# design.net
KiCad netlist of a schematic drawn in Altium Designer
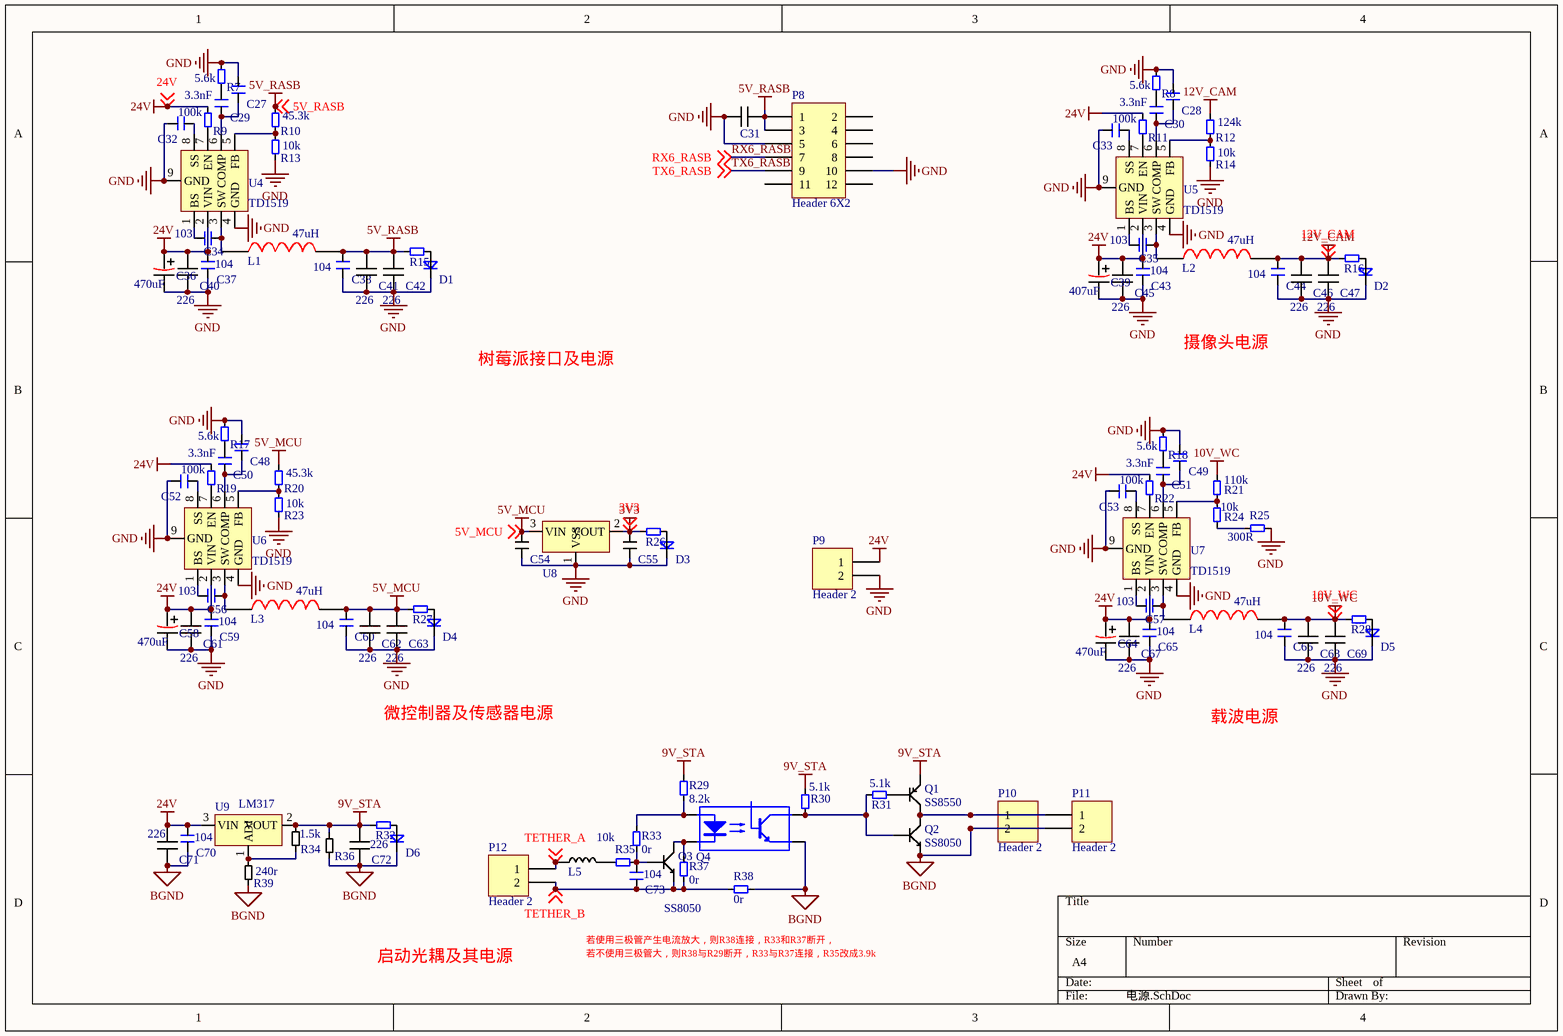
[diagram p0: 电源.SchDoc]

(export (version "E")
  (design (tool "Eeschema 10.0.6"))
  (components
    (comp (ref "C27") (value "0603C") (footprint "0603C") (libsource (lib "水下去机器人控制板2020") (part "0603C")))
    (comp (ref "C28") (value "0603C") (footprint "0603C") (libsource (lib "水下去机器人控制板2020") (part "0603C")))
    (comp (ref "C29")
      (value "0603C")
      (footprint "0603C")
      (fields (field (name "PARAMETER 1") "3.3nF"))
      (libsource (lib "水下去机器人控制板2020") (part "0603C"))
    )
    (comp (ref "C30")
      (value "0603C")
      (footprint "0603C")
      (fields (field (name "PARAMETER 1") "3.3nF"))
      (libsource (lib "水下去机器人控制板2020") (part "0603C"))
    )
    (comp (ref "C31") (value "1206C") (footprint "固态电容5*9") (libsource (lib "水下去机器人控制板2020") (part "1206C")))
    (comp (ref "C32") (value "0603C") (footprint "0603C") (libsource (lib "水下去机器人控制板2020") (part "0603C")))
    (comp (ref "C33") (value "0603C") (footprint "0603C") (libsource (lib "水下去机器人控制板2020") (part "0603C")))
    (comp (ref "C34")
      (value "0603C")
      (footprint "0603C")
      (fields (field (name "PARAMETER 1") "103"))
      (libsource (lib "水下去机器人控制板2020") (part "0603C"))
    )
    (comp (ref "C35")
      (value "0603C")
      (footprint "0603C")
      (fields (field (name "PARAMETER 1") "103"))
      (libsource (lib "水下去机器人控制板2020") (part "0603C"))
    )
    (comp (ref "C36")
      (value "10*10贴片电解电容")
      (footprint "CAP-10*10.2")
      (fields (field (name "PARAMETER 1") "470uF"))
      (libsource (lib "水下去机器人控制板2020") (part "10*10贴片电解电容"))
    )
    (comp (ref "C37")
      (value "0603C")
      (footprint "0603C")
      (fields (field (name "PARAMETER 1") "104"))
      (libsource (lib "水下去机器人控制板2020") (part "0603C"))
    )
    (comp (ref "C38")
      (value "0603C")
      (footprint "0603C")
      (fields (field (name "PARAMETER 1") "104"))
      (libsource (lib "水下去机器人控制板2020") (part "0603C"))
    )
    (comp (ref "C39")
      (value "10*10贴片电解电容")
      (footprint "CAP-10*10.2")
      (fields (field (name "PARAMETER 1") "407uF"))
      (libsource (lib "水下去机器人控制板2020") (part "10*10贴片电解电容"))
    )
    (comp (ref "C40")
      (value "1206C")
      (footprint "1206C")
      (fields (field (name "PARAMETER 1") "226"))
      (libsource (lib "水下去机器人控制板2020") (part "1206C"))
    )
    (comp (ref "C41")
      (value "1206C")
      (footprint "1206C")
      (fields (field (name "PARAMETER 1") "226"))
      (libsource (lib "水下去机器人控制板2020") (part "1206C"))
    )
    (comp (ref "C42")
      (value "1206C")
      (footprint "1206C")
      (fields (field (name "PARAMETER 1") "226"))
      (libsource (lib "水下去机器人控制板2020") (part "1206C"))
    )
    (comp (ref "C43")
      (value "0603C")
      (footprint "0603C")
      (fields (field (name "PARAMETER 1") "104"))
      (libsource (lib "水下去机器人控制板2020") (part "0603C"))
    )
    (comp (ref "C44")
      (value "0603C")
      (footprint "0603C")
      (fields (field (name "PARAMETER 1") "104"))
      (libsource (lib "水下去机器人控制板2020") (part "0603C"))
    )
    (comp (ref "C45")
      (value "1206C")
      (footprint "1206C")
      (fields (field (name "PARAMETER 1") "226"))
      (libsource (lib "水下去机器人控制板2020") (part "1206C"))
    )
    (comp (ref "C46")
      (value "1206C")
      (footprint "1206C")
      (fields (field (name "PARAMETER 1") "226"))
      (libsource (lib "水下去机器人控制板2020") (part "1206C"))
    )
    (comp (ref "C47")
      (value "1206C")
      (footprint "1206C")
      (fields (field (name "PARAMETER 1") "226"))
      (libsource (lib "水下去机器人控制板2020") (part "1206C"))
    )
    (comp (ref "C48") (value "0603C") (footprint "0603C") (libsource (lib "水下去机器人控制板2020") (part "0603C")))
    (comp (ref "C49") (value "0603C") (footprint "0603C") (libsource (lib "水下去机器人控制板2020") (part "0603C")))
    (comp (ref "C50")
      (value "0603C")
      (footprint "0603C")
      (fields (field (name "PARAMETER 1") "3.3nF"))
      (libsource (lib "水下去机器人控制板2020") (part "0603C"))
    )
    (comp (ref "C51")
      (value "0603C")
      (footprint "0603C")
      (fields (field (name "PARAMETER 1") "3.3nF"))
      (libsource (lib "水下去机器人控制板2020") (part "0603C"))
    )
    (comp (ref "C52") (value "0603C") (footprint "0603C") (libsource (lib "水下去机器人控制板2020") (part "0603C")))
    (comp (ref "C53") (value "0603C") (footprint "0603C") (libsource (lib "水下去机器人控制板2020") (part "0603C")))
    (comp (ref "C54") (value "0805C") (footprint "0805C") (libsource (lib "水下去机器人控制板2020") (part "0805C")))
    (comp (ref "C55") (value "0805C") (footprint "0805C") (libsource (lib "水下去机器人控制板2020") (part "0805C")))
    (comp (ref "C56")
      (value "0603C")
      (footprint "0603C")
      (fields (field (name "PARAMETER 1") "103"))
      (libsource (lib "水下去机器人控制板2020") (part "0603C"))
    )
    (comp (ref "C57")
      (value "0603C")
      (footprint "0603C")
      (fields (field (name "PARAMETER 1") "103"))
      (libsource (lib "水下去机器人控制板2020") (part "0603C"))
    )
    (comp (ref "C58")
      (value "10*10贴片电解电容")
      (footprint "CAP-10*10.2")
      (fields (field (name "PARAMETER 1") "470uF"))
      (libsource (lib "水下去机器人控制板2020") (part "10*10贴片电解电容"))
    )
    (comp (ref "C59")
      (value "0603C")
      (footprint "0603C")
      (fields (field (name "PARAMETER 1") "104"))
      (libsource (lib "水下去机器人控制板2020") (part "0603C"))
    )
    (comp (ref "C60")
      (value "0603C")
      (footprint "0603C")
      (fields (field (name "PARAMETER 1") "104"))
      (libsource (lib "水下去机器人控制板2020") (part "0603C"))
    )
    (comp (ref "C61")
      (value "1206C")
      (footprint "1206C")
      (fields (field (name "PARAMETER 1") "226"))
      (libsource (lib "水下去机器人控制板2020") (part "1206C"))
    )
    (comp (ref "C62")
      (value "1206C")
      (footprint "1206C")
      (fields (field (name "PARAMETER 1") "226"))
      (libsource (lib "水下去机器人控制板2020") (part "1206C"))
    )
    (comp (ref "C63")
      (value "1206C")
      (footprint "1206C")
      (fields (field (name "PARAMETER 1") "226"))
      (libsource (lib "水下去机器人控制板2020") (part "1206C"))
    )
    (comp (ref "C64")
      (value "10*10贴片电解电容")
      (footprint "CAP-10*10.2")
      (fields (field (name "PARAMETER 1") "470uF"))
      (libsource (lib "水下去机器人控制板2020") (part "10*10贴片电解电容"))
    )
    (comp (ref "C65")
      (value "0603C")
      (footprint "0603C")
      (fields (field (name "PARAMETER 1") "104"))
      (libsource (lib "水下去机器人控制板2020") (part "0603C"))
    )
    (comp (ref "C66")
      (value "0603C")
      (footprint "0603C")
      (fields (field (name "PARAMETER 1") "104"))
      (libsource (lib "水下去机器人控制板2020") (part "0603C"))
    )
    (comp (ref "C67")
      (value "1206C")
      (footprint "1206C")
      (fields (field (name "PARAMETER 1") "226"))
      (libsource (lib "水下去机器人控制板2020") (part "1206C"))
    )
    (comp (ref "C68")
      (value "1206C")
      (footprint "1206C")
      (fields (field (name "PARAMETER 1") "226"))
      (libsource (lib "水下去机器人控制板2020") (part "1206C"))
    )
    (comp (ref "C69")
      (value "1206C")
      (footprint "1206C")
      (fields (field (name "PARAMETER 1") "226"))
      (libsource (lib "水下去机器人控制板2020") (part "1206C"))
    )
    (comp (ref "C70")
      (value "0603C")
      (footprint "0603C")
      (fields (field (name "PARAMETER 1") "104"))
      (libsource (lib "水下去机器人控制板2020") (part "0603C"))
    )
    (comp (ref "C71")
      (value "1206C")
      (footprint "1206C")
      (fields (field (name "PARAMETER 1") "226"))
      (libsource (lib "水下去机器人控制板2020") (part "1206C"))
    )
    (comp (ref "C72")
      (value "1206C")
      (footprint "1206C")
      (fields (field (name "PARAMETER 1") "226"))
      (libsource (lib "水下去机器人控制板2020") (part "1206C"))
    )
    (comp (ref "C73")
      (value "0603C")
      (footprint "0603C")
      (fields (field (name "PARAMETER 1") "104"))
      (libsource (lib "水下去机器人控制板2020") (part "0603C"))
    )
    (comp (ref "D1") (value "0603D") (footprint "0603D") (libsource (lib "水下去机器人控制板2020") (part "0603D")))
    (comp (ref "D2") (value "0603D") (footprint "0603D") (libsource (lib "水下去机器人控制板2020") (part "0603D")))
    (comp (ref "D3") (value "0603D") (footprint "0603D") (libsource (lib "水下去机器人控制板2020") (part "0603D")))
    (comp (ref "D4") (value "0603D") (footprint "0603D") (libsource (lib "水下去机器人控制板2020") (part "0603D")))
    (comp (ref "D5") (value "0603D") (footprint "0603D") (libsource (lib "水下去机器人控制板2020") (part "0603D")))
    (comp (ref "D6") (value "0603D") (footprint "0603D") (libsource (lib "水下去机器人控制板2020") (part "0603D")))
    (comp (ref "L1")
      (value "1265L")
      (footprint "1265L")
      (fields (field (name "PARAMETER 1") "47uH"))
      (libsource (lib "水下去机器人控制板2020") (part "1265L"))
    )
    (comp (ref "L2")
      (value "1265L")
      (footprint "1265L")
      (fields (field (name "PARAMETER 1") "47uH"))
      (libsource (lib "水下去机器人控制板2020") (part "1265L"))
    )
    (comp (ref "L3")
      (value "1265L")
      (footprint "1265L")
      (fields (field (name "PARAMETER 1") "47uH"))
      (libsource (lib "水下去机器人控制板2020") (part "1265L"))
    )
    (comp (ref "L4")
      (value "1265L")
      (footprint "1265L")
      (fields (field (name "PARAMETER 1") "47uH"))
      (libsource (lib "水下去机器人控制板2020") (part "1265L"))
    )
    (comp (ref "L5") (value "0805L") (footprint "0805L") (libsource (lib "水下去机器人控制板2020") (part "0805L")))
    (comp (ref "P8")
      (value "Header 6X2")
      (footprint "HDR2X6")
      (description "Header, 6-Pin, Dual row")
      (fields (field (name "PUBLISHER") "Altium Limited"))
      (libsource (lib "Miscellaneous Connectors") (part "Header 6X2"))
    )
    (comp (ref "P9")
      (value "Header 2")
      (footprint "DB129")
      (description "Header, 2-Pin")
      (fields (field (name "PUBLISHER") "Altium Limited"))
      (libsource (lib "Miscellaneous Connectors") (part "Header 2"))
    )
    (comp (ref "P10")
      (value "Header 2")
      (footprint "HDR1X2")
      (description "Header, 2-Pin")
      (fields (field (name "PUBLISHER") "Altium Limited"))
      (libsource (lib "") (part "Header 2_1"))
    )
    (comp (ref "P11")
      (value "Header 2")
      (footprint "HDR1X2")
      (description "Header, 2-Pin")
      (fields (field (name "PUBLISHER") "Altium Limited"))
      (libsource (lib "") (part "Header 2_1"))
    )
    (comp (ref "P12")
      (value "Header 2")
      (footprint "DB129")
      (description "Header, 2-Pin")
      (fields (field (name "PUBLISHER") "Altium Limited"))
      (libsource (lib "Miscellaneous Connectors") (part "Header 2"))
    )
    (comp (ref "Q1") (value "SS8550") (footprint "SOT23-3") (libsource (lib "水下去机器人控制板2020") (part "SS8550")))
    (comp (ref "Q2") (value "SS8050") (footprint "SOT23-3") (libsource (lib "水下去机器人控制板2020") (part "SS8050")))
    (comp (ref "Q3") (value "SS8050") (footprint "SOT23-3") (libsource (lib "水下去机器人控制板2020") (part "SS8050")))
    (comp (ref "Q4") (value "光耦") (footprint "DIP4") (libsource (lib "水下去机器人控制板2020") (part "LTV-8141S")))
    (comp (ref "R7")
      (value "0603R")
      (footprint "0603R")
      (fields (field (name "PARAMETER 1") "5.6k"))
      (libsource (lib "水下去机器人控制板2020") (part "0603R"))
    )
    (comp (ref "R8")
      (value "0603R")
      (footprint "0603R")
      (fields (field (name "PARAMETER 1") "5.6k"))
      (libsource (lib "水下去机器人控制板2020") (part "0603R"))
    )
    (comp (ref "R9")
      (value "0603R")
      (footprint "0603R")
      (fields (field (name "PARAMETER 1") "100k"))
      (libsource (lib "水下去机器人控制板2020") (part "0603R"))
    )
    (comp (ref "R10")
      (value "0603R")
      (footprint "0603R")
      (fields (field (name "PARAMETER 1") "45.3k"))
      (libsource (lib "水下去机器人控制板2020") (part "0603R"))
    )
    (comp (ref "R11")
      (value "0603R")
      (footprint "0603R")
      (fields (field (name "PARAMETER 1") "100k"))
      (libsource (lib "水下去机器人控制板2020") (part "0603R"))
    )
    (comp (ref "R12")
      (value "0603R")
      (footprint "0603R")
      (fields (field (name "PARAMETER 1") "124k"))
      (libsource (lib "水下去机器人控制板2020") (part "0603R"))
    )
    (comp (ref "R13")
      (value "0603R")
      (footprint "0603R")
      (fields (field (name "PARAMETER 1") "10k"))
      (libsource (lib "水下去机器人控制板2020") (part "0603R"))
    )
    (comp (ref "R14")
      (value "0603R")
      (footprint "0603R")
      (fields (field (name "PARAMETER 1") "10k"))
      (libsource (lib "水下去机器人控制板2020") (part "0603R"))
    )
    (comp (ref "R15") (value "0603R") (footprint "0603R") (libsource (lib "水下去机器人控制板2020") (part "0603R")))
    (comp (ref "R16") (value "0603R") (footprint "0603R") (libsource (lib "水下去机器人控制板2020") (part "0603R")))
    (comp (ref "R17")
      (value "0603R")
      (footprint "0603R")
      (fields (field (name "PARAMETER 1") "5.6k"))
      (libsource (lib "水下去机器人控制板2020") (part "0603R"))
    )
    (comp (ref "R18")
      (value "0603R")
      (footprint "0603R")
      (fields (field (name "PARAMETER 1") "5.6k"))
      (libsource (lib "水下去机器人控制板2020") (part "0603R"))
    )
    (comp (ref "R19")
      (value "0603R")
      (footprint "0603R")
      (fields (field (name "PARAMETER 1") "100k"))
      (libsource (lib "水下去机器人控制板2020") (part "0603R"))
    )
    (comp (ref "R20")
      (value "0603R")
      (footprint "0603R")
      (fields (field (name "PARAMETER 1") "45.3k"))
      (libsource (lib "水下去机器人控制板2020") (part "0603R"))
    )
    (comp (ref "R21")
      (value "0603R")
      (footprint "0603R")
      (fields (field (name "PARAMETER 1") "110k"))
      (libsource (lib "水下去机器人控制板2020") (part "0603R"))
    )
    (comp (ref "R22")
      (value "0603R")
      (footprint "0603R")
      (fields (field (name "PARAMETER 1") "100k"))
      (libsource (lib "水下去机器人控制板2020") (part "0603R"))
    )
    (comp (ref "R23")
      (value "0603R")
      (footprint "0603R")
      (fields (field (name "PARAMETER 1") "10k"))
      (libsource (lib "水下去机器人控制板2020") (part "0603R"))
    )
    (comp (ref "R24")
      (value "0603R")
      (footprint "0603R")
      (fields (field (name "PARAMETER 1") "10k"))
      (libsource (lib "水下去机器人控制板2020") (part "0603R"))
    )
    (comp (ref "R25")
      (value "0603R")
      (footprint "0603R")
      (fields (field (name "PARAMETER 1") "300R"))
      (libsource (lib "水下去机器人控制板2020") (part "0603R"))
    )
    (comp (ref "R26") (value "0603R") (footprint "0603R") (libsource (lib "水下去机器人控制板2020") (part "0603R")))
    (comp (ref "R27") (value "0603R") (footprint "0603R") (libsource (lib "水下去机器人控制板2020") (part "0603R")))
    (comp (ref "R28") (value "0603R") (footprint "0603R") (libsource (lib "水下去机器人控制板2020") (part "0603R")))
    (comp (ref "R29")
      (value "0603R")
      (footprint "0603R")
      (fields (field (name "PARAMETER 1") "8.2k"))
      (libsource (lib "水下去机器人控制板2020") (part "0603R"))
    )
    (comp (ref "R30")
      (value "0603R")
      (footprint "0603R")
      (fields (field (name "PARAMETER 1") "5.1k"))
      (libsource (lib "水下去机器人控制板2020") (part "0603R"))
    )
    (comp (ref "R31")
      (value "0603R")
      (footprint "0603R")
      (fields (field (name "PARAMETER 1") "5.1k"))
      (libsource (lib "水下去机器人控制板2020") (part "0603R"))
    )
    (comp (ref "R32") (value "0603R") (footprint "0603R") (libsource (lib "水下去机器人控制板2020") (part "0603R")))
    (comp (ref "R33")
      (value "0603R")
      (footprint "0603R")
      (fields (field (name "PARAMETER 1") "0r"))
      (libsource (lib "水下去机器人控制板2020") (part "0603R"))
    )
    (comp (ref "R34")
      (value "0805R")
      (footprint "0805R")
      (fields (field (name "PARAMETER 1") "1.5k"))
      (libsource (lib "水下去机器人控制板2020") (part "0805R"))
    )
    (comp (ref "R35")
      (value "0603R")
      (footprint "0603R")
      (fields (field (name "PARAMETER 1") "10k"))
      (libsource (lib "水下去机器人控制板2020") (part "0603R"))
    )
    (comp (ref "R36") (value "0805R") (footprint "0805R") (libsource (lib "水下去机器人控制板2020") (part "0805R")))
    (comp (ref "R37")
      (value "0603R")
      (footprint "0603R")
      (fields (field (name "PARAMETER 1") "0r"))
      (libsource (lib "水下去机器人控制板2020") (part "0603R"))
    )
    (comp (ref "R38")
      (value "0603R")
      (footprint "0603R")
      (fields (field (name "PARAMETER 1") "0r"))
      (libsource (lib "水下去机器人控制板2020") (part "0603R"))
    )
    (comp (ref "R39")
      (value "0805R")
      (footprint "0805R")
      (fields (field (name "PARAMETER 1") "240r"))
      (libsource (lib "水下去机器人控制板2020") (part "0805R"))
    )
    (comp (ref "U4")
      (value "TD1519")
      (footprint "SOP8-PAD")
      (libsource (lib "水下去机器人控制板2020") (part "TD1519"))
    )
    (comp (ref "U5")
      (value "TD1519")
      (footprint "SOP8-PAD")
      (libsource (lib "水下去机器人控制板2020") (part "TD1519"))
    )
    (comp (ref "U6")
      (value "TD1519")
      (footprint "SOP8-PAD")
      (libsource (lib "水下去机器人控制板2020") (part "TD1519"))
    )
    (comp (ref "U7")
      (value "TD1519")
      (footprint "SOP8-PAD")
      (libsource (lib "水下去机器人控制板2020") (part "TD1519"))
    )
    (comp (ref "U8") (value "662k") (footprint "SOT23-3") (libsource (lib "水下去机器人控制板2020") (part "662k")))
    (comp (ref "U9") (value "LM317") (footprint "TO252-3") (libsource (lib "水下去机器人控制板2020") (part "LM317")))
  )
  (nets
    (net (code "1") (name "3V3") (class "Default")
      (node (ref "C55") (pin "2") (pinfunction "2_2") (pintype "passive"))
      (node (ref "R26") (pin "1") (pinfunction "1_1") (pintype "passive"))
      (node (ref "U8") (pin "2") (pinfunction "VOUT_2") (pintype "passive"))
    )
    (net (code "2") (name "5V_MCU") (class "Default")
      (node (ref "C54") (pin "2") (pinfunction "2_2") (pintype "passive"))
      (node (ref "C60") (pin "2") (pinfunction "2_2") (pintype "passive"))
      (node (ref "C62") (pin "1") (pinfunction "1_1") (pintype "passive"))
      (node (ref "C63") (pin "1") (pinfunction "1_1") (pintype "passive"))
      (node (ref "L3") (pin "2") (pinfunction "2_2") (pintype "passive"))
      (node (ref "R20") (pin "2") (pinfunction "2_2") (pintype "passive"))
      (node (ref "R27") (pin "1") (pinfunction "1_1") (pintype "passive"))
      (node (ref "U8") (pin "3") (pinfunction "VIN_3") (pintype "passive"))
    )
    (net (code "3") (name "5V_RASB") (class "Default")
      (node (ref "C31") (pin "2") (pinfunction "2_2") (pintype "passive"))
      (node (ref "C38") (pin "2") (pinfunction "2_2") (pintype "passive"))
      (node (ref "C41") (pin "1") (pinfunction "1_1") (pintype "passive"))
      (node (ref "C42") (pin "1") (pinfunction "1_1") (pintype "passive"))
      (node (ref "L1") (pin "2") (pinfunction "2_2") (pintype "passive"))
      (node (ref "P8") (pin "1") (pinfunction "1_1") (pintype "passive"))
      (node (ref "P8") (pin "3") (pinfunction "3_3") (pintype "passive"))
      (node (ref "R10") (pin "2") (pinfunction "2_2") (pintype "passive"))
      (node (ref "R15") (pin "1") (pinfunction "1_1") (pintype "passive"))
    )
    (net (code "4") (name "9V_STA") (class "Default")
      (node (ref "C72") (pin "1") (pinfunction "1_1") (pintype "passive"))
      (node (ref "Q1") (pin "2") (pinfunction "E_2") (pintype "passive"))
      (node (ref "R29") (pin "1") (pinfunction "1_1") (pintype "passive"))
      (node (ref "R30") (pin "1") (pinfunction "1_1") (pintype "passive"))
      (node (ref "R32") (pin "1") (pinfunction "1_1") (pintype "passive"))
      (node (ref "R34") (pin "2") (pinfunction "2_2") (pintype "passive"))
      (node (ref "R36") (pin "2") (pinfunction "2_2") (pintype "passive"))
      (node (ref "U9") (pin "2") (pinfunction "VOUT_2") (pintype "passive"))
    )
    (net (code "5") (name "10V_WC") (class "Default")
      (node (ref "C66") (pin "2") (pinfunction "2_2") (pintype "passive"))
      (node (ref "C68") (pin "1") (pinfunction "1_1") (pintype "passive"))
      (node (ref "C69") (pin "1") (pinfunction "1_1") (pintype "passive"))
      (node (ref "L4") (pin "2") (pinfunction "2_2") (pintype "passive"))
      (node (ref "R21") (pin "2") (pinfunction "2_2") (pintype "passive"))
      (node (ref "R28") (pin "1") (pinfunction "1_1") (pintype "passive"))
    )
    (net (code "6") (name "12V_CAM") (class "Default")
      (node (ref "C44") (pin "2") (pinfunction "2_2") (pintype "passive"))
      (node (ref "C46") (pin "1") (pinfunction "1_1") (pintype "passive"))
      (node (ref "C47") (pin "1") (pinfunction "1_1") (pintype "passive"))
      (node (ref "L2") (pin "2") (pinfunction "2_2") (pintype "passive"))
      (node (ref "R12") (pin "2") (pinfunction "2_2") (pintype "passive"))
      (node (ref "R16") (pin "1") (pinfunction "1_1") (pintype "passive"))
    )
    (net (code "7") (name "24V") (class "Default")
      (node (ref "C36") (pin "1") (pinfunction "1_1") (pintype "passive"))
      (node (ref "C37") (pin "2") (pinfunction "2_2") (pintype "passive"))
      (node (ref "C39") (pin "1") (pinfunction "1_1") (pintype "passive"))
      (node (ref "C40") (pin "1") (pinfunction "1_1") (pintype "passive"))
      (node (ref "C43") (pin "2") (pinfunction "2_2") (pintype "passive"))
      (node (ref "C45") (pin "1") (pinfunction "1_1") (pintype "passive"))
      (node (ref "C58") (pin "1") (pinfunction "1_1") (pintype "passive"))
      (node (ref "C59") (pin "2") (pinfunction "2_2") (pintype "passive"))
      (node (ref "C61") (pin "1") (pinfunction "1_1") (pintype "passive"))
      (node (ref "C64") (pin "1") (pinfunction "1_1") (pintype "passive"))
      (node (ref "C65") (pin "2") (pinfunction "2_2") (pintype "passive"))
      (node (ref "C67") (pin "1") (pinfunction "1_1") (pintype "passive"))
      (node (ref "C70") (pin "2") (pinfunction "2_2") (pintype "passive"))
      (node (ref "C71") (pin "1") (pinfunction "1_1") (pintype "passive"))
      (node (ref "P9") (pin "1") (pinfunction "1_1") (pintype "passive"))
      (node (ref "R11") (pin "2") (pinfunction "2_2") (pintype "passive"))
      (node (ref "R19") (pin "2") (pinfunction "2_2") (pintype "passive"))
      (node (ref "R22") (pin "2") (pinfunction "2_2") (pintype "passive"))
      (node (ref "R9") (pin "2") (pinfunction "2_2") (pintype "passive"))
      (node (ref "U4") (pin "2") (pinfunction "VIN_2") (pintype "power_in"))
      (node (ref "U5") (pin "2") (pinfunction "VIN_2") (pintype "power_in"))
      (node (ref "U6") (pin "2") (pinfunction "VIN_2") (pintype "power_in"))
      (node (ref "U7") (pin "2") (pinfunction "VIN_2") (pintype "power_in"))
      (node (ref "U9") (pin "3") (pinfunction "VIN_3") (pintype "passive"))
    )
    (net (code "8") (name "BGND") (class "Default")
      (node (ref "C70") (pin "1") (pinfunction "1_1") (pintype "passive"))
      (node (ref "C71") (pin "2") (pinfunction "2_2") (pintype "passive"))
      (node (ref "C72") (pin "2") (pinfunction "2_2") (pintype "passive"))
      (node (ref "D6") (pin "2") (pinfunction "2_2") (pintype "passive"))
      (node (ref "P10") (pin "2") (pinfunction "2_2") (pintype "passive"))
      (node (ref "P11") (pin "2") (pinfunction "2_2") (pintype "passive"))
      (node (ref "Q2") (pin "2") (pinfunction "E_2") (pintype "passive"))
      (node (ref "Q4") (pin "3") (pinfunction "Emitter_3") (pintype "passive"))
      (node (ref "R36") (pin "1") (pinfunction "1_1") (pintype "passive"))
      (node (ref "R38") (pin "2") (pinfunction "2_2") (pintype "passive"))
      (node (ref "R39") (pin "1") (pinfunction "1_1") (pintype "passive"))
    )
    (net (code "9") (name "GND") (class "Default")
      (node (ref "C27") (pin "1") (pinfunction "1_1") (pintype "passive"))
      (node (ref "C28") (pin "1") (pinfunction "1_1") (pintype "passive"))
      (node (ref "C31") (pin "1") (pinfunction "1_1") (pintype "passive"))
      (node (ref "C32") (pin "2") (pinfunction "2_2") (pintype "passive"))
      (node (ref "C33") (pin "2") (pinfunction "2_2") (pintype "passive"))
      (node (ref "C36") (pin "2") (pinfunction "2_2") (pintype "passive"))
      (node (ref "C37") (pin "1") (pinfunction "1_1") (pintype "passive"))
      (node (ref "C38") (pin "1") (pinfunction "1_1") (pintype "passive"))
      (node (ref "C39") (pin "2") (pinfunction "2_2") (pintype "passive"))
      (node (ref "C40") (pin "2") (pinfunction "2_2") (pintype "passive"))
      (node (ref "C41") (pin "2") (pinfunction "2_2") (pintype "passive"))
      (node (ref "C42") (pin "2") (pinfunction "2_2") (pintype "passive"))
      (node (ref "C43") (pin "1") (pinfunction "1_1") (pintype "passive"))
      (node (ref "C44") (pin "1") (pinfunction "1_1") (pintype "passive"))
      (node (ref "C45") (pin "2") (pinfunction "2_2") (pintype "passive"))
      (node (ref "C46") (pin "2") (pinfunction "2_2") (pintype "passive"))
      (node (ref "C47") (pin "2") (pinfunction "2_2") (pintype "passive"))
      (node (ref "C48") (pin "1") (pinfunction "1_1") (pintype "passive"))
      (node (ref "C49") (pin "1") (pinfunction "1_1") (pintype "passive"))
      (node (ref "C52") (pin "2") (pinfunction "2_2") (pintype "passive"))
      (node (ref "C53") (pin "2") (pinfunction "2_2") (pintype "passive"))
      (node (ref "C54") (pin "1") (pinfunction "1_1") (pintype "passive"))
      (node (ref "C55") (pin "1") (pinfunction "1_1") (pintype "passive"))
      (node (ref "C58") (pin "2") (pinfunction "2_2") (pintype "passive"))
      (node (ref "C59") (pin "1") (pinfunction "1_1") (pintype "passive"))
      (node (ref "C60") (pin "1") (pinfunction "1_1") (pintype "passive"))
      (node (ref "C61") (pin "2") (pinfunction "2_2") (pintype "passive"))
      (node (ref "C62") (pin "2") (pinfunction "2_2") (pintype "passive"))
      (node (ref "C63") (pin "2") (pinfunction "2_2") (pintype "passive"))
      (node (ref "C64") (pin "2") (pinfunction "2_2") (pintype "passive"))
      (node (ref "C65") (pin "1") (pinfunction "1_1") (pintype "passive"))
      (node (ref "C66") (pin "1") (pinfunction "1_1") (pintype "passive"))
      (node (ref "C67") (pin "2") (pinfunction "2_2") (pintype "passive"))
      (node (ref "C68") (pin "2") (pinfunction "2_2") (pintype "passive"))
      (node (ref "C69") (pin "2") (pinfunction "2_2") (pintype "passive"))
      (node (ref "D1") (pin "2") (pinfunction "2_2") (pintype "passive"))
      (node (ref "D2") (pin "2") (pinfunction "2_2") (pintype "passive"))
      (node (ref "D3") (pin "2") (pinfunction "2_2") (pintype "passive"))
      (node (ref "D4") (pin "2") (pinfunction "2_2") (pintype "passive"))
      (node (ref "D5") (pin "2") (pinfunction "2_2") (pintype "passive"))
      (node (ref "P8") (pin "10") (pinfunction "10_10") (pintype "passive"))
      (node (ref "P8") (pin "5") (pinfunction "5_5") (pintype "passive"))
      (node (ref "P9") (pin "2") (pinfunction "2_2") (pintype "passive"))
      (node (ref "R13") (pin "1") (pinfunction "1_1") (pintype "passive"))
      (node (ref "R14") (pin "1") (pinfunction "1_1") (pintype "passive"))
      (node (ref "R17") (pin "2") (pinfunction "2_2") (pintype "passive"))
      (node (ref "R18") (pin "2") (pinfunction "2_2") (pintype "passive"))
      (node (ref "R23") (pin "1") (pinfunction "1_1") (pintype "passive"))
      (node (ref "R25") (pin "1") (pinfunction "1_1") (pintype "passive"))
      (node (ref "R7") (pin "2") (pinfunction "2_2") (pintype "passive"))
      (node (ref "R8") (pin "2") (pinfunction "2_2") (pintype "passive"))
      (node (ref "U4") (pin "4") (pinfunction "GND_4") (pintype "power_in"))
      (node (ref "U4") (pin "9") (pinfunction "GND_9") (pintype "power_in"))
      (node (ref "U5") (pin "4") (pinfunction "GND_4") (pintype "power_in"))
      (node (ref "U5") (pin "9") (pinfunction "GND_9") (pintype "power_in"))
      (node (ref "U6") (pin "4") (pinfunction "GND_4") (pintype "power_in"))
      (node (ref "U6") (pin "9") (pinfunction "GND_9") (pintype "power_in"))
      (node (ref "U7") (pin "4") (pinfunction "GND_4") (pintype "power_in"))
      (node (ref "U7") (pin "9") (pinfunction "GND_9") (pintype "power_in"))
      (node (ref "U8") (pin "1") (pinfunction "VSS_1") (pintype "passive"))
    )
    (net (code "10") (name "Net-(C29-Pad1)") (class "Default")
      (node (ref "C29") (pin "1") (pinfunction "1_1") (pintype "passive"))
      (node (ref "R7") (pin "1") (pinfunction "1_1") (pintype "passive"))
    )
    (net (code "11") (name "Net-(C30-Pad1)") (class "Default")
      (node (ref "C30") (pin "1") (pinfunction "1_1") (pintype "passive"))
      (node (ref "R8") (pin "1") (pinfunction "1_1") (pintype "passive"))
    )
    (net (code "12") (name "Net-(C50-Pad1)") (class "Default")
      (node (ref "C50") (pin "1") (pinfunction "1_1") (pintype "passive"))
      (node (ref "R17") (pin "1") (pinfunction "1_1") (pintype "passive"))
    )
    (net (code "13") (name "Net-(C51-Pad1)") (class "Default")
      (node (ref "C51") (pin "1") (pinfunction "1_1") (pintype "passive"))
      (node (ref "R18") (pin "1") (pinfunction "1_1") (pintype "passive"))
    )
    (net (code "14") (name "Net-(D1-Pad1)") (class "Default")
      (node (ref "D1") (pin "1") (pinfunction "1_1") (pintype "passive"))
      (node (ref "R15") (pin "2") (pinfunction "2_2") (pintype "passive"))
    )
    (net (code "15") (name "Net-(D2-Pad1)") (class "Default")
      (node (ref "D2") (pin "1") (pinfunction "1_1") (pintype "passive"))
      (node (ref "R16") (pin "2") (pinfunction "2_2") (pintype "passive"))
    )
    (net (code "16") (name "Net-(D3-Pad1)") (class "Default")
      (node (ref "D3") (pin "1") (pinfunction "1_1") (pintype "passive"))
      (node (ref "R26") (pin "2") (pinfunction "2_2") (pintype "passive"))
    )
    (net (code "17") (name "Net-(D4-Pad1)") (class "Default")
      (node (ref "D4") (pin "1") (pinfunction "1_1") (pintype "passive"))
      (node (ref "R27") (pin "2") (pinfunction "2_2") (pintype "passive"))
    )
    (net (code "18") (name "Net-(D5-Pad1)") (class "Default")
      (node (ref "D5") (pin "1") (pinfunction "1_1") (pintype "passive"))
      (node (ref "R28") (pin "2") (pinfunction "2_2") (pintype "passive"))
    )
    (net (code "19") (name "Net-(D6-Pad1)") (class "Default")
      (node (ref "D6") (pin "1") (pinfunction "1_1") (pintype "passive"))
      (node (ref "R32") (pin "2") (pinfunction "2_2") (pintype "passive"))
    )
    (net (code "20") (name "Net-(L5-Pad2)") (class "Default")
      (node (ref "L5") (pin "2") (pinfunction "2_2") (pintype "passive"))
      (node (ref "R35") (pin "2") (pinfunction "2_2") (pintype "passive"))
    )
    (net (code "21") (name "Net-(Q1-B)") (class "Default")
      (node (ref "Q1") (pin "1") (pinfunction "B_1") (pintype "passive"))
      (node (ref "R31") (pin "2") (pinfunction "2_2") (pintype "passive"))
    )
    (net (code "22") (name "Net-(Q1-C)") (class "Default")
      (node (ref "P10") (pin "1") (pinfunction "1_1") (pintype "passive"))
      (node (ref "P11") (pin "1") (pinfunction "1_1") (pintype "passive"))
      (node (ref "Q1") (pin "3") (pinfunction "C_3") (pintype "passive"))
      (node (ref "Q2") (pin "3") (pinfunction "C_3") (pintype "passive"))
    )
    (net (code "23") (name "Net-(Q2-B)") (class "Default")
      (node (ref "Q2") (pin "1") (pinfunction "B_1") (pintype "passive"))
      (node (ref "Q4") (pin "4") (pinfunction "Collector_4") (pintype "passive"))
      (node (ref "R30") (pin "2") (pinfunction "2_2") (pintype "passive"))
      (node (ref "R31") (pin "1") (pinfunction "1_1") (pintype "passive"))
    )
    (net (code "24") (name "Net-(Q3-B)") (class "Default")
      (node (ref "C73") (pin "2") (pinfunction "2_2") (pintype "passive"))
      (node (ref "Q3") (pin "1") (pinfunction "B_1") (pintype "passive"))
      (node (ref "R33") (pin "1") (pinfunction "1_1") (pintype "passive"))
      (node (ref "R35") (pin "1") (pinfunction "1_1") (pintype "passive"))
    )
    (net (code "25") (name "Net-(Q3-C)") (class "Default")
      (node (ref "Q3") (pin "3") (pinfunction "C_3") (pintype "passive"))
      (node (ref "Q4") (pin "2") (pinfunction "LED_Cathode_2") (pintype "passive"))
      (node (ref "R37") (pin "2") (pinfunction "2_2") (pintype "passive"))
    )
    (net (code "26") (name "Net-(Q4-LED_Anode)") (class "Default")
      (node (ref "Q4") (pin "1") (pinfunction "LED_Anode_1") (pintype "passive"))
      (node (ref "R29") (pin "2") (pinfunction "2_2") (pintype "passive"))
      (node (ref "R33") (pin "2") (pinfunction "2_2") (pintype "passive"))
    )
    (net (code "27") (name "Net-(R24-Pad1)") (class "Default")
      (node (ref "R24") (pin "1") (pinfunction "1_1") (pintype "passive"))
      (node (ref "R25") (pin "2") (pinfunction "2_2") (pintype "passive"))
    )
    (net (code "28") (name "Net-(U4-BS)") (class "Default")
      (node (ref "C34") (pin "2") (pinfunction "2_2") (pintype "passive"))
      (node (ref "U4") (pin "1") (pinfunction "BS_1") (pintype "power_in"))
    )
    (net (code "29") (name "Net-(U4-COMP)") (class "Default")
      (node (ref "C27") (pin "2") (pinfunction "2_2") (pintype "passive"))
      (node (ref "C29") (pin "2") (pinfunction "2_2") (pintype "passive"))
      (node (ref "U4") (pin "6") (pinfunction "COMP_6") (pintype "power_in"))
    )
    (net (code "30") (name "Net-(U4-EN)") (class "Default")
      (node (ref "R9") (pin "1") (pinfunction "1_1") (pintype "passive"))
      (node (ref "U4") (pin "7") (pinfunction "EN_7") (pintype "power_in"))
    )
    (net (code "31") (name "Net-(U4-FB)") (class "Default")
      (node (ref "R10") (pin "1") (pinfunction "1_1") (pintype "passive"))
      (node (ref "R13") (pin "2") (pinfunction "2_2") (pintype "passive"))
      (node (ref "U4") (pin "5") (pinfunction "FB_5") (pintype "power_in"))
    )
    (net (code "32") (name "Net-(U4-SS)") (class "Default")
      (node (ref "C32") (pin "1") (pinfunction "1_1") (pintype "passive"))
      (node (ref "U4") (pin "8") (pinfunction "SS_8") (pintype "power_in"))
    )
    (net (code "33") (name "Net-(U4-SW)") (class "Default")
      (node (ref "C34") (pin "1") (pinfunction "1_1") (pintype "passive"))
      (node (ref "L1") (pin "1") (pinfunction "1_1") (pintype "passive"))
      (node (ref "U4") (pin "3") (pinfunction "SW_3") (pintype "power_in"))
    )
    (net (code "34") (name "Net-(U5-BS)") (class "Default")
      (node (ref "C35") (pin "2") (pinfunction "2_2") (pintype "passive"))
      (node (ref "U5") (pin "1") (pinfunction "BS_1") (pintype "power_in"))
    )
    (net (code "35") (name "Net-(U5-COMP)") (class "Default")
      (node (ref "C28") (pin "2") (pinfunction "2_2") (pintype "passive"))
      (node (ref "C30") (pin "2") (pinfunction "2_2") (pintype "passive"))
      (node (ref "U5") (pin "6") (pinfunction "COMP_6") (pintype "power_in"))
    )
    (net (code "36") (name "Net-(U5-EN)") (class "Default")
      (node (ref "R11") (pin "1") (pinfunction "1_1") (pintype "passive"))
      (node (ref "U5") (pin "7") (pinfunction "EN_7") (pintype "power_in"))
    )
    (net (code "37") (name "Net-(U5-FB)") (class "Default")
      (node (ref "R12") (pin "1") (pinfunction "1_1") (pintype "passive"))
      (node (ref "R14") (pin "2") (pinfunction "2_2") (pintype "passive"))
      (node (ref "U5") (pin "5") (pinfunction "FB_5") (pintype "power_in"))
    )
    (net (code "38") (name "Net-(U5-SS)") (class "Default")
      (node (ref "C33") (pin "1") (pinfunction "1_1") (pintype "passive"))
      (node (ref "U5") (pin "8") (pinfunction "SS_8") (pintype "power_in"))
    )
    (net (code "39") (name "Net-(U5-SW)") (class "Default")
      (node (ref "C35") (pin "1") (pinfunction "1_1") (pintype "passive"))
      (node (ref "L2") (pin "1") (pinfunction "1_1") (pintype "passive"))
      (node (ref "U5") (pin "3") (pinfunction "SW_3") (pintype "power_in"))
    )
    (net (code "40") (name "Net-(U6-BS)") (class "Default")
      (node (ref "C56") (pin "2") (pinfunction "2_2") (pintype "passive"))
      (node (ref "U6") (pin "1") (pinfunction "BS_1") (pintype "power_in"))
    )
    (net (code "41") (name "Net-(U6-COMP)") (class "Default")
      (node (ref "C48") (pin "2") (pinfunction "2_2") (pintype "passive"))
      (node (ref "C50") (pin "2") (pinfunction "2_2") (pintype "passive"))
      (node (ref "U6") (pin "6") (pinfunction "COMP_6") (pintype "power_in"))
    )
    (net (code "42") (name "Net-(U6-EN)") (class "Default")
      (node (ref "R19") (pin "1") (pinfunction "1_1") (pintype "passive"))
      (node (ref "U6") (pin "7") (pinfunction "EN_7") (pintype "power_in"))
    )
    (net (code "43") (name "Net-(U6-FB)") (class "Default")
      (node (ref "R20") (pin "1") (pinfunction "1_1") (pintype "passive"))
      (node (ref "R23") (pin "2") (pinfunction "2_2") (pintype "passive"))
      (node (ref "U6") (pin "5") (pinfunction "FB_5") (pintype "power_in"))
    )
    (net (code "44") (name "Net-(U6-SS)") (class "Default")
      (node (ref "C52") (pin "1") (pinfunction "1_1") (pintype "passive"))
      (node (ref "U6") (pin "8") (pinfunction "SS_8") (pintype "power_in"))
    )
    (net (code "45") (name "Net-(U6-SW)") (class "Default")
      (node (ref "C56") (pin "1") (pinfunction "1_1") (pintype "passive"))
      (node (ref "L3") (pin "1") (pinfunction "1_1") (pintype "passive"))
      (node (ref "U6") (pin "3") (pinfunction "SW_3") (pintype "power_in"))
    )
    (net (code "46") (name "Net-(U7-BS)") (class "Default")
      (node (ref "C57") (pin "2") (pinfunction "2_2") (pintype "passive"))
      (node (ref "U7") (pin "1") (pinfunction "BS_1") (pintype "power_in"))
    )
    (net (code "47") (name "Net-(U7-COMP)") (class "Default")
      (node (ref "C49") (pin "2") (pinfunction "2_2") (pintype "passive"))
      (node (ref "C51") (pin "2") (pinfunction "2_2") (pintype "passive"))
      (node (ref "U7") (pin "6") (pinfunction "COMP_6") (pintype "power_in"))
    )
    (net (code "48") (name "Net-(U7-EN)") (class "Default")
      (node (ref "R22") (pin "1") (pinfunction "1_1") (pintype "passive"))
      (node (ref "U7") (pin "7") (pinfunction "EN_7") (pintype "power_in"))
    )
    (net (code "49") (name "Net-(U7-FB)") (class "Default")
      (node (ref "R21") (pin "1") (pinfunction "1_1") (pintype "passive"))
      (node (ref "R24") (pin "2") (pinfunction "2_2") (pintype "passive"))
      (node (ref "U7") (pin "5") (pinfunction "FB_5") (pintype "power_in"))
    )
    (net (code "50") (name "Net-(U7-SS)") (class "Default")
      (node (ref "C53") (pin "1") (pinfunction "1_1") (pintype "passive"))
      (node (ref "U7") (pin "8") (pinfunction "SS_8") (pintype "power_in"))
    )
    (net (code "51") (name "Net-(U7-SW)") (class "Default")
      (node (ref "C57") (pin "1") (pinfunction "1_1") (pintype "passive"))
      (node (ref "L4") (pin "1") (pinfunction "1_1") (pintype "passive"))
      (node (ref "U7") (pin "3") (pinfunction "SW_3") (pintype "power_in"))
    )
    (net (code "52") (name "Net-(U9-ADJ)") (class "Default")
      (node (ref "R34") (pin "1") (pinfunction "1_1") (pintype "passive"))
      (node (ref "R39") (pin "2") (pinfunction "2_2") (pintype "passive"))
      (node (ref "U9") (pin "1") (pinfunction "ADJ_1") (pintype "passive"))
    )
    (net (code "53") (name "RX6_RASB") (class "Default")
      (node (ref "P8") (pin "7") (pinfunction "7_7") (pintype "passive"))
    )
    (net (code "54") (name "TETHER_A") (class "Default")
      (node (ref "L5") (pin "1") (pinfunction "1_1") (pintype "passive"))
      (node (ref "P12") (pin "1") (pinfunction "1_1") (pintype "passive"))
    )
    (net (code "55") (name "TETHER_B") (class "Default")
      (node (ref "C73") (pin "1") (pinfunction "1_1") (pintype "passive"))
      (node (ref "P12") (pin "2") (pinfunction "2_2") (pintype "passive"))
      (node (ref "Q3") (pin "2") (pinfunction "E_2") (pintype "passive"))
      (node (ref "R37") (pin "1") (pinfunction "1_1") (pintype "passive"))
      (node (ref "R38") (pin "1") (pinfunction "1_1") (pintype "passive"))
    )
    (net (code "56") (name "TX6_RASB") (class "Default")
      (node (ref "P8") (pin "9") (pinfunction "9_9") (pintype "passive"))
    )
    (net (code "57") (name "unconnected-(P8-Pad2)") (class "Default")
      (node (ref "P8") (pin "2") (pinfunction "2_2") (pintype "passive"))
    )
    (net (code "58") (name "unconnected-(P8-Pad4)") (class "Default")
      (node (ref "P8") (pin "4") (pinfunction "4_4") (pintype "passive"))
    )
    (net (code "59") (name "unconnected-(P8-Pad6)") (class "Default")
      (node (ref "P8") (pin "6") (pinfunction "6_6") (pintype "passive"))
    )
    (net (code "60") (name "unconnected-(P8-Pad8)") (class "Default")
      (node (ref "P8") (pin "8") (pinfunction "8_8") (pintype "passive"))
    )
    (net (code "61") (name "unconnected-(P8-Pad11)") (class "Default")
      (node (ref "P8") (pin "11") (pinfunction "11_11") (pintype "passive"))
    )
    (net (code "62") (name "unconnected-(P8-Pad12)") (class "Default")
      (node (ref "P8") (pin "12") (pinfunction "12_12") (pintype "passive"))
    )
  )
)
